# Watch-It-Board-1.net
KiCad netlist of a schematic drawn in EAGLE
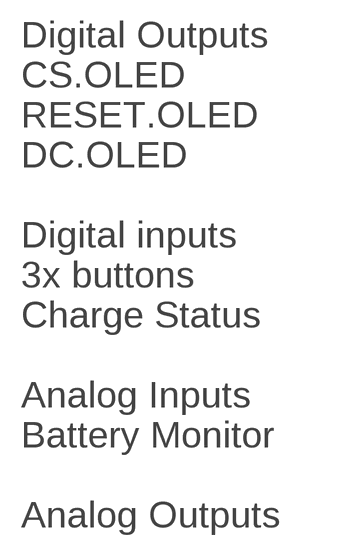
[diagram p0: schematic, sheet 1, part 1 of 2]
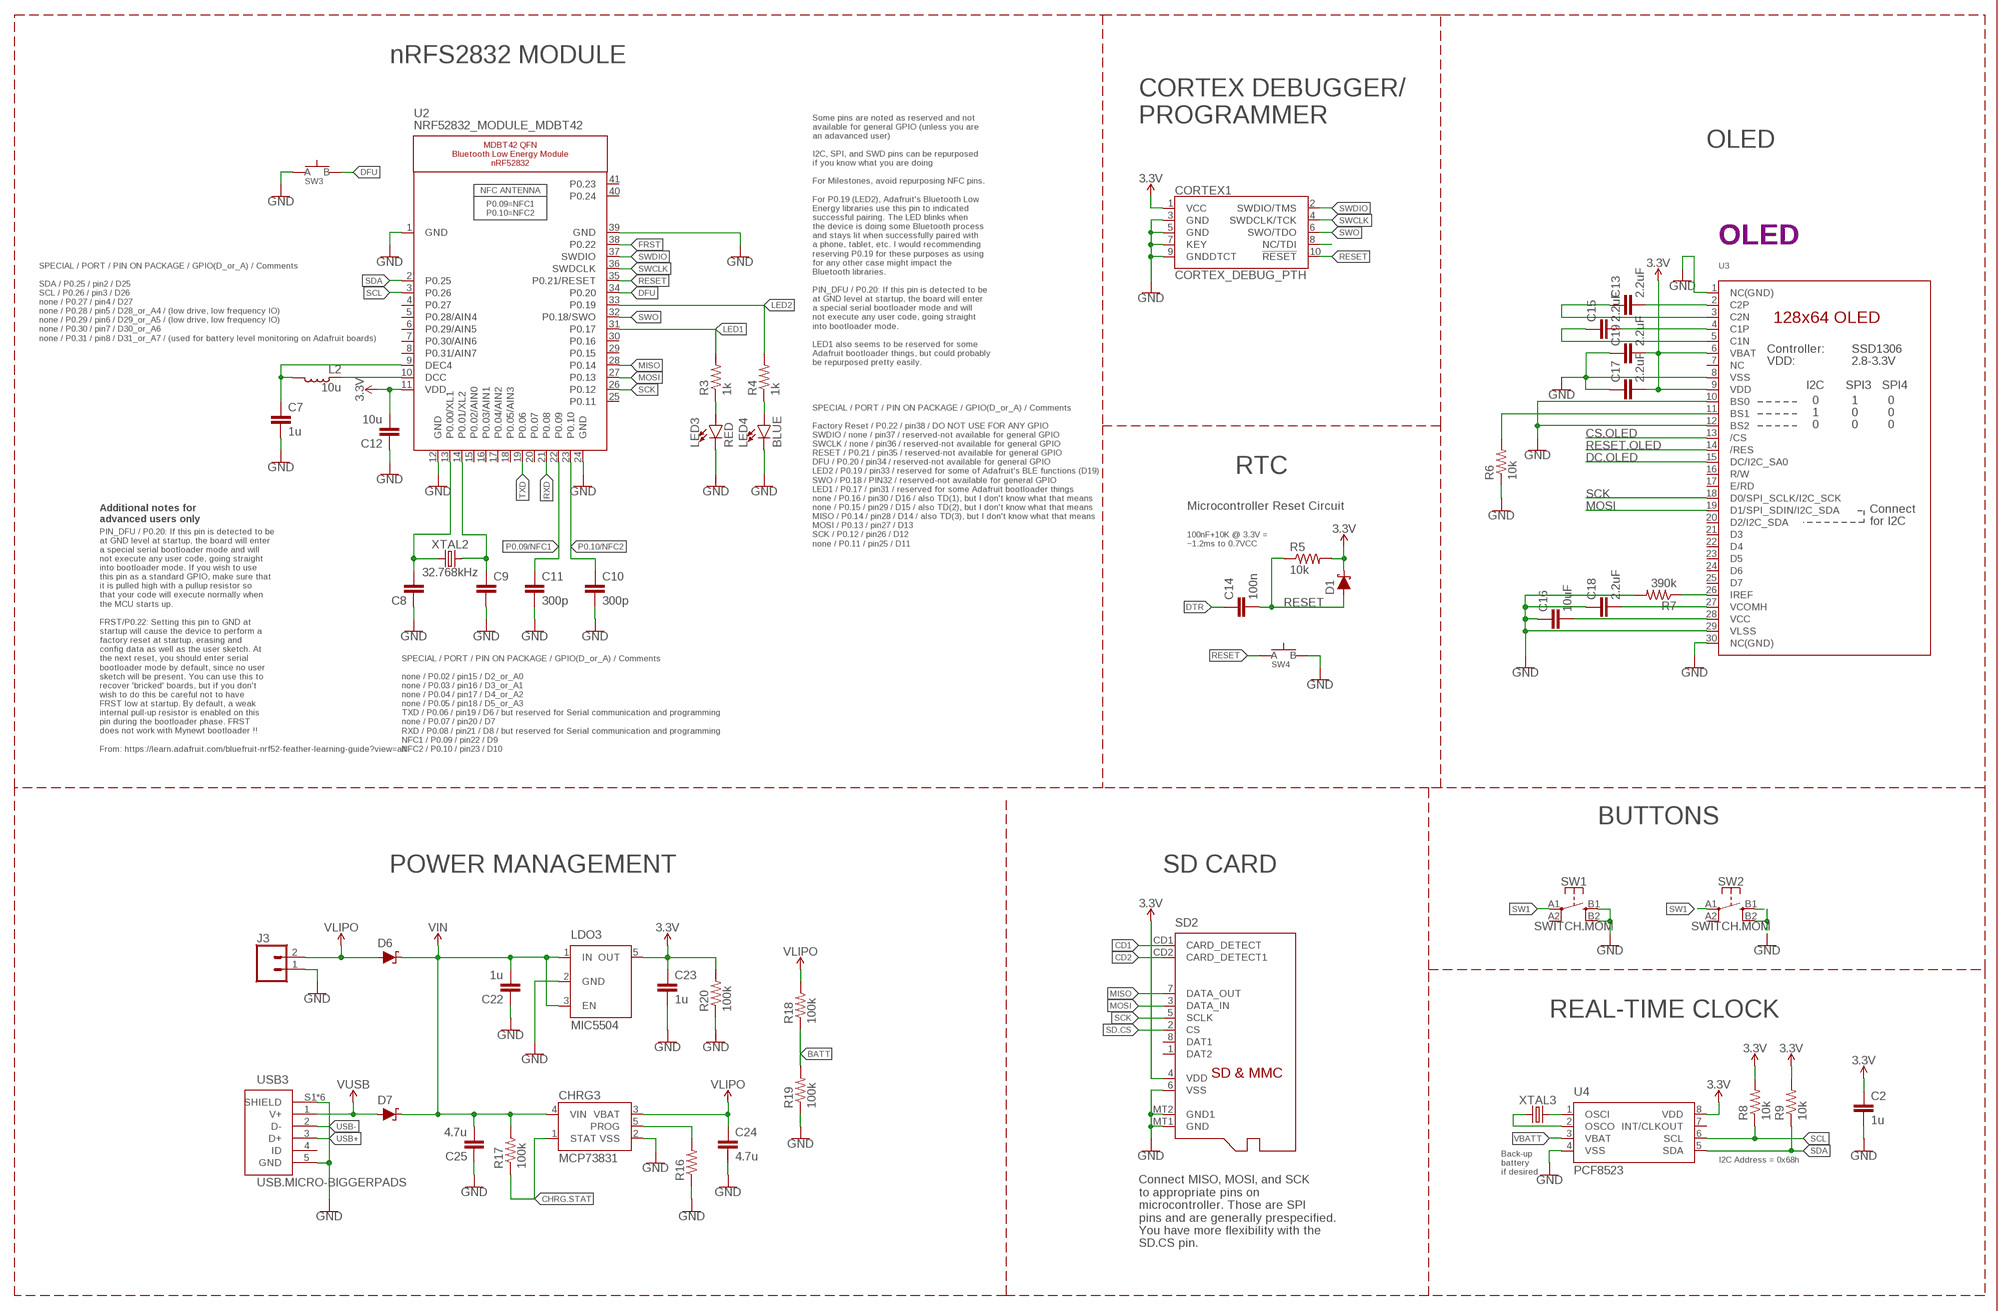
[diagram p1: schematic, sheet 1, part 2 of 2]

(export (version "E")
  (design (tool "Eeschema 10.0.6"))
  (components
    (comp (ref "C2")
      (value "1u")
      (footprint "eagle-import:C0603")
      (libsource (lib "eagle-import") (part "CAPACITOR0603"))
    )
    (comp (ref "C7")
      (value "1u")
      (footprint "eagle-import:C0603")
      (libsource (lib "eagle-import") (part "CAPACITOR0603"))
    )
    (comp (ref "C8")
      (value "CAPACITOR0603")
      (footprint "eagle-import:C0603")
      (libsource (lib "eagle-import") (part "CAPACITOR0603"))
    )
    (comp (ref "C9")
      (value "CAPACITOR0603")
      (footprint "eagle-import:C0603")
      (libsource (lib "eagle-import") (part "CAPACITOR0603"))
    )
    (comp (ref "C10")
      (value "300p")
      (footprint "eagle-import:C0603")
      (libsource (lib "eagle-import") (part "CAPACITOR0603"))
    )
    (comp (ref "C11")
      (value "300p")
      (footprint "eagle-import:C0603")
      (libsource (lib "eagle-import") (part "CAPACITOR0603"))
    )
    (comp (ref "C12")
      (value "10u")
      (footprint "eagle-import:C0805")
      (libsource (lib "eagle-import") (part "CAPACITOR0805"))
    )
    (comp (ref "C13")
      (value "2.2uF")
      (footprint "eagle-import:C0402")
      (libsource (lib "eagle-import") (part "CAPACITOR0402"))
    )
    (comp (ref "C14")
      (value "100n")
      (footprint "eagle-import:C0603")
      (libsource (lib "eagle-import") (part "CAPACITOR0603"))
    )
    (comp (ref "C15")
      (value "2.2uF")
      (footprint "eagle-import:C0402")
      (libsource (lib "eagle-import") (part "CAPACITOR0402"))
    )
    (comp (ref "C16")
      (value "10uF")
      (footprint "eagle-import:C0603")
      (libsource (lib "eagle-import") (part "CAPACITOR0603"))
    )
    (comp (ref "C17")
      (value "2.2uF")
      (footprint "eagle-import:C0402")
      (libsource (lib "eagle-import") (part "CAPACITOR0402"))
    )
    (comp (ref "C18")
      (value "2.2uF")
      (footprint "eagle-import:C0402")
      (libsource (lib "eagle-import") (part "CAPACITOR0402"))
    )
    (comp (ref "C19")
      (value "2.2uF")
      (footprint "eagle-import:C0402")
      (libsource (lib "eagle-import") (part "CAPACITOR0402"))
    )
    (comp (ref "C22")
      (value "1u")
      (footprint "eagle-import:C0603")
      (libsource (lib "eagle-import") (part "CAPACITOR0603"))
    )
    (comp (ref "C23")
      (value "1u")
      (footprint "eagle-import:C0603")
      (libsource (lib "eagle-import") (part "CAPACITOR0603"))
    )
    (comp (ref "C24")
      (value "4.7u")
      (footprint "eagle-import:C0603")
      (libsource (lib "eagle-import") (part "CAPACITOR0603"))
    )
    (comp (ref "C25")
      (value "4.7u")
      (footprint "eagle-import:C0603")
      (libsource (lib "eagle-import") (part "CAPACITOR0603"))
    )
    (comp (ref "CHRG3")
      (value "MCP73831")
      (footprint "eagle-import:SOT23-5")
      (libsource (lib "eagle-import") (part "MCP73831"))
    )
    (comp (ref "CORTEX1")
      (value "CORTEX_DEBUG_PTH")
      (footprint "eagle-import:2X5-PTH-1.27MM")
      (libsource (lib "eagle-import") (part "CORTEX_DEBUG_PTH"))
    )
    (comp (ref "D1")
      (value "SCHOTTKY-USC")
      (footprint "eagle-import:USC")
      (libsource (lib "eagle-import") (part "SCHOTTKY-USC"))
    )
    (comp (ref "D6")
      (value "SCHOTTKY-USC")
      (footprint "eagle-import:USC")
      (libsource (lib "eagle-import") (part "SCHOTTKY-USC"))
    )
    (comp (ref "D7")
      (value "SCHOTTKY-USC")
      (footprint "eagle-import:USC")
      (libsource (lib "eagle-import") (part "SCHOTTKY-USC"))
    )
    (comp (ref "J3")
      (value "CONN_02")
      (footprint "eagle-import:1X02")
      (libsource (lib "eagle-import") (part "CONN_02"))
    )
    (comp (ref "L2")
      (value "10u")
      (footprint "eagle-import:L0603")
      (libsource (lib "eagle-import") (part "INDUCTOR0603"))
    )
    (comp (ref "LDO3")
      (value "MIC5504")
      (footprint "eagle-import:SOT23-5")
      (libsource (lib "eagle-import") (part "MIC5504"))
    )
    (comp (ref "LED3")
      (value "RED")
      (footprint "eagle-import:LED-0603")
      (libsource (lib "eagle-import") (part "LED0603"))
    )
    (comp (ref "LED4")
      (value "BLUE")
      (footprint "eagle-import:LED-0603")
      (libsource (lib "eagle-import") (part "LED0603"))
    )
    (comp (ref "R3")
      (value "1k")
      (footprint "eagle-import:R0603")
      (libsource (lib "eagle-import") (part "RESISTOR0603"))
    )
    (comp (ref "R4")
      (value "1k")
      (footprint "eagle-import:R0603")
      (libsource (lib "eagle-import") (part "RESISTOR0603"))
    )
    (comp (ref "R5")
      (value "10k")
      (footprint "eagle-import:R0603")
      (libsource (lib "eagle-import") (part "RESISTOR0603"))
    )
    (comp (ref "R6")
      (value "10k")
      (footprint "eagle-import:R0603")
      (libsource (lib "eagle-import") (part "RESISTOR0603"))
    )
    (comp (ref "R7")
      (value "390k")
      (footprint "eagle-import:R0603")
      (libsource (lib "eagle-import") (part "RESISTOR0603"))
    )
    (comp (ref "R8")
      (value "10k")
      (footprint "eagle-import:R0603")
      (libsource (lib "eagle-import") (part "RESISTOR0603"))
    )
    (comp (ref "R9")
      (value "10k")
      (footprint "eagle-import:R0603")
      (libsource (lib "eagle-import") (part "RESISTOR0603"))
    )
    (comp (ref "R16")
      (value "RESISTOR0603")
      (footprint "eagle-import:R0603")
      (libsource (lib "eagle-import") (part "RESISTOR0603"))
    )
    (comp (ref "R17")
      (value "100k")
      (footprint "eagle-import:R0603")
      (libsource (lib "eagle-import") (part "RESISTOR0603"))
    )
    (comp (ref "R18")
      (value "100k")
      (footprint "eagle-import:R0603")
      (libsource (lib "eagle-import") (part "RESISTOR0603"))
    )
    (comp (ref "R19")
      (value "100k")
      (footprint "eagle-import:R0603")
      (libsource (lib "eagle-import") (part "RESISTOR0603"))
    )
    (comp (ref "R20")
      (value "100k")
      (footprint "eagle-import:R0603")
      (libsource (lib "eagle-import") (part "RESISTOR0603"))
    )
    (comp (ref "SD2")
      (value "MICROSD")
      (footprint "eagle-import:MICROSD")
      (libsource (lib "eagle-import") (part "MICROSD"))
    )
    (comp (ref "SW1")
      (value "SWITCH.MOM")
      (footprint "eagle-import:TACTILE_SWITCH_SMD_6.2MM_TALL")
      (libsource (lib "eagle-import") (part "SWITCH.MOM"))
    )
    (comp (ref "SW2")
      (value "SWITCH.MOM")
      (footprint "eagle-import:TACTILE_SWITCH_SMD_6.2MM_TALL")
      (libsource (lib "eagle-import") (part "SWITCH.MOM"))
    )
    (comp (ref "SW3")
      (value "SPST-PTS830GG140-COPY.1-3")
      (footprint "eagle-import:BUTTON-GULLWING")
      (libsource (lib "eagle-import") (part "SPST-PTS830GG140-COPY.1-3"))
    )
    (comp (ref "SW4")
      (value "SPST-PTS830GG140-COPY.1-3")
      (footprint "eagle-import:BUTTON-GULLWING")
      (libsource (lib "eagle-import") (part "SPST-PTS830GG140-COPY.1-3"))
    )
    (comp (ref "U2")
      (value "NRF52832_MODULE_MDBT42")
      (footprint "eagle-import:BLE_MODULE_RAYTAC_MDBT42")
      (libsource (lib "eagle-import") (part "NRF52832_MODULE_MDBT42"))
    )
    (comp (ref "U3")
      (value "DISP_OLED_UG-2864HSWEG01-NO-WRAPAROUND")
      (footprint "eagle-import:UG-2864HSWEG01_0.96IN_NO-WRAPAROUND")
      (libsource (lib "eagle-import") (part "DISP_OLED_UG-2864HSWEG01-NO-WRAPAROUND"))
    )
    (comp (ref "U4")
      (value "PCF8523")
      (footprint "eagle-import:SO8")
      (libsource (lib "eagle-import") (part "PCF8523"))
    )
    (comp (ref "USB3")
      (value "USB.MICRO-BIGGERPADS")
      (footprint "eagle-import:USB-MICRO-01.BIGGERPADS")
      (libsource (lib "eagle-import") (part "USB.MICRO-BIGGERPADS"))
    )
    (comp (ref "XTAL2")
      (value "32.768kHz")
      (footprint "eagle-import:2-SMD.NOLEAD.2.0MMTO1.2MM")
      (libsource (lib "eagle-import") (part "CRYSTALECS-.327-12.5-12-C-TR"))
    )
    (comp (ref "XTAL3")
      (value "32.7680kHz")
      (footprint "eagle-import:2-SMD.NOLEAD.2.0MMTO1.2MM")
      (fields (field (name "FREQ") "32.7680KHZ"))
      (libsource (lib "eagle-import") (part "CRYSTALECS-.327-12.5-12-C-TR"))
    )
  )
  (nets
    (net (code "1") (name "/CS.OLED") (class "Default")
      (node (ref "U3") (pin "13") (pinfunction "/CS_13") (pintype "input"))
    )
    (net (code "2") (name "/DC.OLED") (class "Default")
      (node (ref "U3") (pin "15") (pinfunction "DC/I2C_SA0_15") (pintype "input"))
    )
    (net (code "3") (name "/RESET.OLED") (class "Default")
      (node (ref "U3") (pin "14") (pinfunction "/RES_14") (pintype "input"))
    )
    (net (code "4") (name "3.3V") (class "Default")
      (node (ref "C12") (pin "2") (pinfunction "2_2") (pintype "passive"))
      (node (ref "C17") (pin "2") (pinfunction "2_2") (pintype "passive"))
      (node (ref "C19") (pin "2") (pinfunction "2_2") (pintype "passive"))
      (node (ref "C2") (pin "1") (pinfunction "1_1") (pintype "passive"))
      (node (ref "C23") (pin "1") (pinfunction "1_1") (pintype "passive"))
      (node (ref "CORTEX1") (pin "1") (pinfunction "VCC_1") (pintype "bidirectional"))
      (node (ref "D1") (pin "-") (pinfunction "C_-") (pintype "passive"))
      (node (ref "LDO3") (pin "5") (pinfunction "OUT_5") (pintype "bidirectional"))
      (node (ref "R20") (pin "2") (pinfunction "2_2") (pintype "passive"))
      (node (ref "R5") (pin "2") (pinfunction "2_2") (pintype "passive"))
      (node (ref "R8") (pin "2") (pinfunction "2_2") (pintype "passive"))
      (node (ref "R9") (pin "2") (pinfunction "2_2") (pintype "passive"))
      (node (ref "SD2") (pin "4") (pinfunction "VDD_4") (pintype "power_in"))
      (node (ref "U2") (pin "11") (pinfunction "VDD_11") (pintype "bidirectional"))
      (node (ref "U3") (pin "6") (pinfunction "VBAT_6") (pintype "input"))
      (node (ref "U3") (pin "9") (pinfunction "VDD_9") (pintype "power_in"))
      (node (ref "U4") (pin "8") (pinfunction "VDD_8") (pintype "power_in"))
    )
    (net (code "5") (name "BATT") (class "Default")
      (node (ref "R18") (pin "1") (pinfunction "1_1") (pintype "passive"))
      (node (ref "R19") (pin "2") (pinfunction "2_2") (pintype "passive"))
    )
    (net (code "6") (name "CD1") (class "Default")
      (node (ref "SD2") (pin "CD1") (pinfunction "CARD_DETECT_CD1") (pintype "passive"))
    )
    (net (code "7") (name "CD2") (class "Default")
      (node (ref "SD2") (pin "CD2") (pinfunction "CARD_DETECT1_CD2") (pintype "passive"))
    )
    (net (code "8") (name "CHRG.STAT") (class "Default")
      (node (ref "CHRG3") (pin "1") (pinfunction "STAT_1") (pintype "output"))
      (node (ref "R17") (pin "1") (pinfunction "1_1") (pintype "passive"))
    )
    (net (code "9") (name "DFU") (class "Default")
      (node (ref "SW3") (pin "3") (pinfunction "B_3") (pintype "bidirectional"))
      (node (ref "U2") (pin "34") (pinfunction "P0.20_34") (pintype "bidirectional"))
    )
    (net (code "10") (name "DTR") (class "Default")
      (node (ref "C14") (pin "1") (pinfunction "1_1") (pintype "passive"))
    )
    (net (code "11") (name "FRST") (class "Default")
      (node (ref "U2") (pin "38") (pinfunction "P0.22_38") (pintype "bidirectional"))
    )
    (net (code "12") (name "GND") (class "Default")
      (node (ref "C10") (pin "2") (pinfunction "2_2") (pintype "passive"))
      (node (ref "C11") (pin "2") (pinfunction "2_2") (pintype "passive"))
      (node (ref "C12") (pin "1") (pinfunction "1_1") (pintype "passive"))
      (node (ref "C16") (pin "1") (pinfunction "1_1") (pintype "passive"))
      (node (ref "C17") (pin "1") (pinfunction "1_1") (pintype "passive"))
      (node (ref "C18") (pin "1") (pinfunction "1_1") (pintype "passive"))
      (node (ref "C19") (pin "1") (pinfunction "1_1") (pintype "passive"))
      (node (ref "C2") (pin "2") (pinfunction "2_2") (pintype "passive"))
      (node (ref "C22") (pin "1") (pinfunction "1_1") (pintype "passive"))
      (node (ref "C23") (pin "2") (pinfunction "2_2") (pintype "passive"))
      (node (ref "C24") (pin "2") (pinfunction "2_2") (pintype "passive"))
      (node (ref "C25") (pin "1") (pinfunction "1_1") (pintype "passive"))
      (node (ref "C7") (pin "2") (pinfunction "2_2") (pintype "passive"))
      (node (ref "C8") (pin "1") (pinfunction "1_1") (pintype "passive"))
      (node (ref "C9") (pin "2") (pinfunction "2_2") (pintype "passive"))
      (node (ref "CHRG3") (pin "2") (pinfunction "VSS_2") (pintype "power_in"))
      (node (ref "CORTEX1") (pin "3") (pinfunction "GND_3") (pintype "bidirectional"))
      (node (ref "CORTEX1") (pin "5") (pinfunction "GND_5") (pintype "bidirectional"))
      (node (ref "CORTEX1") (pin "7") (pinfunction "KEY_7") (pintype "bidirectional"))
      (node (ref "CORTEX1") (pin "9") (pinfunction "GNDDTCT_9") (pintype "bidirectional"))
      (node (ref "J3") (pin "1") (pinfunction "1_1") (pintype "passive"))
      (node (ref "LDO3") (pin "2") (pinfunction "GND_2") (pintype "bidirectional"))
      (node (ref "LED3") (pin "C") (pinfunction "C_C") (pintype "passive"))
      (node (ref "LED4") (pin "C") (pinfunction "C_C") (pintype "passive"))
      (node (ref "R16") (pin "1") (pinfunction "1_1") (pintype "passive"))
      (node (ref "R19") (pin "1") (pinfunction "1_1") (pintype "passive"))
      (node (ref "R20") (pin "1") (pinfunction "1_1") (pintype "passive"))
      (node (ref "R6") (pin "1") (pinfunction "1_1") (pintype "passive"))
      (node (ref "R7") (pin "2") (pinfunction "2_2") (pintype "passive"))
      (node (ref "SD2") (pin "6") (pinfunction "VSS_6") (pintype "power_in"))
      (node (ref "SD2") (pin "MT1") (pinfunction "GND_MT1") (pintype "power_in"))
      (node (ref "SD2") (pin "MT2") (pinfunction "GND1_MT2") (pintype "power_in"))
      (node (ref "SW1") (pin "B1") (pinfunction "3_B1") (pintype "passive"))
      (node (ref "SW1") (pin "B2") (pinfunction "4_B2") (pintype "passive"))
      (node (ref "SW2") (pin "B1") (pinfunction "3_B1") (pintype "passive"))
      (node (ref "SW2") (pin "B2") (pinfunction "4_B2") (pintype "passive"))
      (node (ref "SW3") (pin "1") (pinfunction "A_1") (pintype "bidirectional"))
      (node (ref "SW4") (pin "3") (pinfunction "B_3") (pintype "bidirectional"))
      (node (ref "U2") (pin "1") (pinfunction "GND_1") (pintype "bidirectional"))
      (node (ref "U2") (pin "12") (pinfunction "GND_12") (pintype "bidirectional"))
      (node (ref "U2") (pin "24") (pinfunction "GND_24") (pintype "bidirectional"))
      (node (ref "U2") (pin "39") (pinfunction "GND_39") (pintype "bidirectional"))
      (node (ref "U3") (pin "1") (pinfunction "NC(GND)_1") (pintype "input"))
      (node (ref "U3") (pin "10") (pinfunction "BS0_10") (pintype "input"))
      (node (ref "U3") (pin "12") (pinfunction "BS2_12") (pintype "input"))
      (node (ref "U3") (pin "29") (pinfunction "VLSS_29") (pintype "power_in"))
      (node (ref "U3") (pin "30") (pinfunction "NC(GND)_30") (pintype "input"))
      (node (ref "U3") (pin "8") (pinfunction "VSS_8") (pintype "power_in"))
      (node (ref "U4") (pin "4") (pinfunction "VSS_4") (pintype "power_in"))
      (node (ref "USB3") (pin "5") (pinfunction "GND_5") (pintype "bidirectional"))
      (node (ref "USB3") (pin "S1") (pinfunction "SHIELD_S1") (pintype "bidirectional"))
      (node (ref "USB3") (pin "S2") (pinfunction "SHIELD_S2") (pintype "bidirectional"))
      (node (ref "USB3") (pin "S3") (pinfunction "SHIELD_S3") (pintype "bidirectional"))
      (node (ref "USB3") (pin "S4") (pinfunction "SHIELD_S4") (pintype "bidirectional"))
      (node (ref "USB3") (pin "S5") (pinfunction "SHIELD_S5") (pintype "bidirectional"))
      (node (ref "USB3") (pin "S6") (pinfunction "SHIELD_S6") (pintype "bidirectional"))
    )
    (net (code "13") (name "LED1") (class "Default")
      (node (ref "R3") (pin "2") (pinfunction "2_2") (pintype "passive"))
      (node (ref "U2") (pin "31") (pinfunction "P0.17_31") (pintype "bidirectional"))
    )
    (net (code "14") (name "LED2") (class "Default")
      (node (ref "R4") (pin "2") (pinfunction "2_2") (pintype "passive"))
      (node (ref "U2") (pin "33") (pinfunction "P0.19_33") (pintype "bidirectional"))
    )
    (net (code "15") (name "MISO") (class "Default")
      (node (ref "SD2") (pin "7") (pinfunction "DATA_OUT_7") (pintype "output"))
      (node (ref "U2") (pin "28") (pinfunction "P0.14_28") (pintype "bidirectional"))
    )
    (net (code "16") (name "MOSI") (class "Default")
      (node (ref "SD2") (pin "3") (pinfunction "DATA_IN_3") (pintype "input"))
      (node (ref "U2") (pin "27") (pinfunction "P0.13_27") (pintype "bidirectional"))
      (node (ref "U3") (pin "19") (pinfunction "D1/SPI_SDIN/I2C_SDA_19") (pintype "bidirectional"))
    )
    (net (code "17") (name "Net-(CHRG3-PROG)") (class "Default")
      (node (ref "CHRG3") (pin "5") (pinfunction "PROG_5") (pintype "input"))
      (node (ref "R16") (pin "2") (pinfunction "2_2") (pintype "passive"))
    )
    (net (code "18") (name "Net-(LED3-PadA)") (class "Default")
      (node (ref "LED3") (pin "A") (pinfunction "A_A") (pintype "passive"))
      (node (ref "R3") (pin "1") (pinfunction "1_1") (pintype "passive"))
    )
    (net (code "19") (name "Net-(LED4-PadA)") (class "Default")
      (node (ref "LED4") (pin "A") (pinfunction "A_A") (pintype "passive"))
      (node (ref "R4") (pin "1") (pinfunction "1_1") (pintype "passive"))
    )
    (net (code "20") (name "Net-(U2-DCC)") (class "Default")
      (node (ref "L2") (pin "1") (pinfunction "1_1") (pintype "passive"))
      (node (ref "U2") (pin "10") (pinfunction "DCC_10") (pintype "bidirectional"))
    )
    (net (code "21") (name "Net-(U2-DEC4)") (class "Default")
      (node (ref "C7") (pin "1") (pinfunction "1_1") (pintype "passive"))
      (node (ref "L2") (pin "2") (pinfunction "2_2") (pintype "passive"))
      (node (ref "U2") (pin "9") (pinfunction "DEC4_9") (pintype "bidirectional"))
    )
    (net (code "22") (name "Net-(U2-P0.00{slash}XL1)") (class "Default")
      (node (ref "C8") (pin "2") (pinfunction "2_2") (pintype "passive"))
      (node (ref "U2") (pin "13") (pinfunction "P0.00/XL1_13") (pintype "bidirectional"))
      (node (ref "XTAL2") (pin "P$1") (pinfunction "1_P$1") (pintype "passive"))
    )
    (net (code "23") (name "Net-(U2-P0.01{slash}XL2)") (class "Default")
      (node (ref "C9") (pin "1") (pinfunction "1_1") (pintype "passive"))
      (node (ref "U2") (pin "14") (pinfunction "P0.01/XL2_14") (pintype "bidirectional"))
      (node (ref "XTAL2") (pin "P$2") (pinfunction "2_P$2") (pintype "passive"))
    )
    (net (code "24") (name "Net-(U3-BS1)") (class "Default")
      (node (ref "R6") (pin "2") (pinfunction "2_2") (pintype "passive"))
      (node (ref "U3") (pin "11") (pinfunction "BS1_11") (pintype "input"))
    )
    (net (code "25") (name "Net-(U3-C1N)") (class "Default")
      (node (ref "C15") (pin "1") (pinfunction "1_1") (pintype "passive"))
      (node (ref "U3") (pin "5") (pinfunction "C1N_5") (pintype "input"))
    )
    (net (code "26") (name "Net-(U3-C1P)") (class "Default")
      (node (ref "C15") (pin "2") (pinfunction "2_2") (pintype "passive"))
      (node (ref "U3") (pin "4") (pinfunction "C1P_4") (pintype "input"))
    )
    (net (code "27") (name "Net-(U3-C2N)") (class "Default")
      (node (ref "C13") (pin "1") (pinfunction "1_1") (pintype "passive"))
      (node (ref "U3") (pin "3") (pinfunction "C2N_3") (pintype "input"))
    )
    (net (code "28") (name "Net-(U3-C2P)") (class "Default")
      (node (ref "C13") (pin "2") (pinfunction "2_2") (pintype "passive"))
      (node (ref "U3") (pin "2") (pinfunction "C2P_2") (pintype "input"))
    )
    (net (code "29") (name "Net-(U3-IREF)") (class "Default")
      (node (ref "R7") (pin "1") (pinfunction "1_1") (pintype "passive"))
      (node (ref "U3") (pin "26") (pinfunction "IREF_26") (pintype "input"))
    )
    (net (code "30") (name "Net-(U3-VCC)") (class "Default")
      (node (ref "C16") (pin "2") (pinfunction "2_2") (pintype "passive"))
      (node (ref "U3") (pin "28") (pinfunction "VCC_28") (pintype "power_in"))
    )
    (net (code "31") (name "Net-(U3-VCOMH)") (class "Default")
      (node (ref "C18") (pin "2") (pinfunction "2_2") (pintype "passive"))
      (node (ref "U3") (pin "27") (pinfunction "VCOMH_27") (pintype "output"))
    )
    (net (code "32") (name "Net-(U4-OSCI)") (class "Default")
      (node (ref "U4") (pin "1") (pinfunction "OSCI_1") (pintype "bidirectional"))
      (node (ref "XTAL3") (pin "P$2") (pinfunction "2_P$2") (pintype "passive"))
    )
    (net (code "33") (name "Net-(U4-OSCO)") (class "Default")
      (node (ref "U4") (pin "2") (pinfunction "OSCO_2") (pintype "bidirectional"))
      (node (ref "XTAL3") (pin "P$1") (pinfunction "1_P$1") (pintype "passive"))
    )
    (net (code "34") (name "P0.09{slash}NFC1") (class "Default")
      (node (ref "C11") (pin "1") (pinfunction "1_1") (pintype "passive"))
      (node (ref "U2") (pin "22") (pinfunction "P0.09_22") (pintype "bidirectional"))
    )
    (net (code "35") (name "P0.10{slash}NFC2") (class "Default")
      (node (ref "C10") (pin "1") (pinfunction "1_1") (pintype "passive"))
      (node (ref "U2") (pin "23") (pinfunction "P0.10_23") (pintype "bidirectional"))
    )
    (net (code "36") (name "RESET") (class "Default")
      (node (ref "C14") (pin "2") (pinfunction "2_2") (pintype "passive"))
      (node (ref "CORTEX1") (pin "10") (pinfunction "~{RESET}_10") (pintype "bidirectional"))
      (node (ref "D1") (pin "+") (pinfunction "A_+") (pintype "passive"))
      (node (ref "R5") (pin "1") (pinfunction "1_1") (pintype "passive"))
      (node (ref "SW4") (pin "1") (pinfunction "A_1") (pintype "bidirectional"))
      (node (ref "U2") (pin "35") (pinfunction "P0.21/RESET_35") (pintype "bidirectional"))
    )
    (net (code "37") (name "RXD") (class "Default")
      (node (ref "U2") (pin "21") (pinfunction "P0.08_21") (pintype "bidirectional"))
    )
    (net (code "38") (name "SCK") (class "Default")
      (node (ref "SD2") (pin "5") (pinfunction "SCLK_5") (pintype "input"))
      (node (ref "U2") (pin "26") (pinfunction "P0.12_26") (pintype "bidirectional"))
      (node (ref "U3") (pin "18") (pinfunction "D0/SPI_SCLK/I2C_SCK_18") (pintype "bidirectional"))
    )
    (net (code "39") (name "SCL") (class "Default")
      (node (ref "R8") (pin "1") (pinfunction "1_1") (pintype "passive"))
      (node (ref "U2") (pin "3") (pinfunction "P0.26_3") (pintype "bidirectional"))
      (node (ref "U4") (pin "6") (pinfunction "SCL_6") (pintype "bidirectional"))
    )
    (net (code "40") (name "SD.CS") (class "Default")
      (node (ref "SD2") (pin "2") (pinfunction "CS_2") (pintype "input"))
    )
    (net (code "41") (name "SDA") (class "Default")
      (node (ref "R9") (pin "1") (pinfunction "1_1") (pintype "passive"))
      (node (ref "U2") (pin "2") (pinfunction "P0.25_2") (pintype "bidirectional"))
      (node (ref "U4") (pin "5") (pinfunction "SDA_5") (pintype "bidirectional"))
    )
    (net (code "42") (name "SW1") (class "Default")
      (node (ref "SW1") (pin "A1") (pinfunction "1_A1") (pintype "passive"))
      (node (ref "SW2") (pin "A1") (pinfunction "1_A1") (pintype "passive"))
    )
    (net (code "43") (name "SWCLK") (class "Default")
      (node (ref "CORTEX1") (pin "4") (pinfunction "SWDCLK/TCK_4") (pintype "bidirectional"))
      (node (ref "U2") (pin "36") (pinfunction "SWDCLK_36") (pintype "bidirectional"))
    )
    (net (code "44") (name "SWDIO") (class "Default")
      (node (ref "CORTEX1") (pin "2") (pinfunction "SWDIO/TMS_2") (pintype "bidirectional"))
      (node (ref "U2") (pin "37") (pinfunction "SWDIO_37") (pintype "bidirectional"))
    )
    (net (code "45") (name "SWO") (class "Default")
      (node (ref "CORTEX1") (pin "6") (pinfunction "SWO/TDO_6") (pintype "bidirectional"))
      (node (ref "U2") (pin "32") (pinfunction "P0.18/SWO_32") (pintype "bidirectional"))
    )
    (net (code "46") (name "TXD") (class "Default")
      (node (ref "U2") (pin "19") (pinfunction "P0.06_19") (pintype "bidirectional"))
    )
    (net (code "47") (name "USB+") (class "Default")
      (node (ref "USB3") (pin "3") (pinfunction "D+_3") (pintype "bidirectional"))
    )
    (net (code "48") (name "USB-") (class "Default")
      (node (ref "USB3") (pin "2") (pinfunction "D-_2") (pintype "bidirectional"))
    )
    (net (code "49") (name "VBATT") (class "Default")
      (node (ref "U4") (pin "3") (pinfunction "VBAT_3") (pintype "power_in"))
    )
    (net (code "50") (name "VIN") (class "Default")
      (node (ref "C22") (pin "2") (pinfunction "2_2") (pintype "passive"))
      (node (ref "C25") (pin "2") (pinfunction "2_2") (pintype "passive"))
      (node (ref "CHRG3") (pin "4") (pinfunction "VIN_4") (pintype "power_in"))
      (node (ref "D6") (pin "-") (pinfunction "C_-") (pintype "passive"))
      (node (ref "D7") (pin "-") (pinfunction "C_-") (pintype "passive"))
      (node (ref "LDO3") (pin "1") (pinfunction "IN_1") (pintype "bidirectional"))
      (node (ref "LDO3") (pin "3") (pinfunction "EN_3") (pintype "bidirectional"))
      (node (ref "R17") (pin "2") (pinfunction "2_2") (pintype "passive"))
    )
    (net (code "51") (name "VLIPO") (class "Default")
      (node (ref "C24") (pin "1") (pinfunction "1_1") (pintype "passive"))
      (node (ref "CHRG3") (pin "3") (pinfunction "VBAT_3") (pintype "power_in"))
      (node (ref "D6") (pin "+") (pinfunction "A_+") (pintype "passive"))
      (node (ref "J3") (pin "2") (pinfunction "2_2") (pintype "passive"))
      (node (ref "R18") (pin "2") (pinfunction "2_2") (pintype "passive"))
    )
    (net (code "52") (name "VUSB") (class "Default")
      (node (ref "D7") (pin "+") (pinfunction "A_+") (pintype "passive"))
      (node (ref "USB3") (pin "1") (pinfunction "V+_1") (pintype "bidirectional"))
    )
    (net (code "53") (name "unconnected-(CORTEX1-NC{slash}TDI-Pad8)") (class "Default")
      (node (ref "CORTEX1") (pin "8") (pinfunction "NC/TDI_8") (pintype "bidirectional"))
    )
    (net (code "54") (name "unconnected-(SD2-DAT1-Pad8)") (class "Default")
      (node (ref "SD2") (pin "8") (pinfunction "DAT1_8") (pintype "bidirectional"))
    )
    (net (code "55") (name "unconnected-(SD2-DAT2-Pad1)") (class "Default")
      (node (ref "SD2") (pin "1") (pinfunction "DAT2_1") (pintype "bidirectional"))
    )
    (net (code "56") (name "unconnected-(SW1-2-PadA2)") (class "Default")
      (node (ref "SW1") (pin "A2") (pinfunction "2_A2") (pintype "passive"))
    )
    (net (code "57") (name "unconnected-(SW2-2-PadA2)") (class "Default")
      (node (ref "SW2") (pin "A2") (pinfunction "2_A2") (pintype "passive"))
    )
    (net (code "58") (name "unconnected-(U2-P0.02{slash}AIN0-Pad15)") (class "Default")
      (node (ref "U2") (pin "15") (pinfunction "P0.02/AIN0_15") (pintype "bidirectional"))
    )
    (net (code "59") (name "unconnected-(U2-P0.03{slash}AIN1-Pad16)") (class "Default")
      (node (ref "U2") (pin "16") (pinfunction "P0.03/AIN1_16") (pintype "bidirectional"))
    )
    (net (code "60") (name "unconnected-(U2-P0.04{slash}AIN2-Pad17)") (class "Default")
      (node (ref "U2") (pin "17") (pinfunction "P0.04/AIN2_17") (pintype "bidirectional"))
    )
    (net (code "61") (name "unconnected-(U2-P0.05{slash}AIN3-Pad18)") (class "Default")
      (node (ref "U2") (pin "18") (pinfunction "P0.05/AIN3_18") (pintype "bidirectional"))
    )
    (net (code "62") (name "unconnected-(U2-P0.07-Pad20)") (class "Default")
      (node (ref "U2") (pin "20") (pinfunction "P0.07_20") (pintype "bidirectional"))
    )
    (net (code "63") (name "unconnected-(U2-P0.11-Pad25)") (class "Default")
      (node (ref "U2") (pin "25") (pinfunction "P0.11_25") (pintype "bidirectional"))
    )
    (net (code "64") (name "unconnected-(U2-P0.15-Pad29)") (class "Default")
      (node (ref "U2") (pin "29") (pinfunction "P0.15_29") (pintype "bidirectional"))
    )
    (net (code "65") (name "unconnected-(U2-P0.16-Pad30)") (class "Default")
      (node (ref "U2") (pin "30") (pinfunction "P0.16_30") (pintype "bidirectional"))
    )
    (net (code "66") (name "unconnected-(U2-P0.23-Pad41)") (class "Default")
      (node (ref "U2") (pin "41") (pinfunction "P0.23_41") (pintype "bidirectional"))
    )
    (net (code "67") (name "unconnected-(U2-P0.24-Pad40)") (class "Default")
      (node (ref "U2") (pin "40") (pinfunction "P0.24_40") (pintype "bidirectional"))
    )
    (net (code "68") (name "unconnected-(U2-P0.27-Pad4)") (class "Default")
      (node (ref "U2") (pin "4") (pinfunction "P0.27_4") (pintype "bidirectional"))
    )
    (net (code "69") (name "unconnected-(U2-P0.28{slash}AIN4-Pad5)") (class "Default")
      (node (ref "U2") (pin "5") (pinfunction "P0.28/AIN4_5") (pintype "bidirectional"))
    )
    (net (code "70") (name "unconnected-(U2-P0.29{slash}AIN5-Pad6)") (class "Default")
      (node (ref "U2") (pin "6") (pinfunction "P0.29/AIN5_6") (pintype "bidirectional"))
    )
    (net (code "71") (name "unconnected-(U2-P0.30{slash}AIN6-Pad7)") (class "Default")
      (node (ref "U2") (pin "7") (pinfunction "P0.30/AIN6_7") (pintype "bidirectional"))
    )
    (net (code "72") (name "unconnected-(U2-P0.31{slash}AIN7-Pad8)") (class "Default")
      (node (ref "U2") (pin "8") (pinfunction "P0.31/AIN7_8") (pintype "bidirectional"))
    )
    (net (code "73") (name "unconnected-(U3-D2{slash}I2C_SDA-Pad20)") (class "Default")
      (node (ref "U3") (pin "20") (pinfunction "D2/I2C_SDA_20") (pintype "bidirectional"))
    )
    (net (code "74") (name "unconnected-(U3-D3-Pad21)") (class "Default")
      (node (ref "U3") (pin "21") (pinfunction "D3_21") (pintype "bidirectional"))
    )
    (net (code "75") (name "unconnected-(U3-D4-Pad22)") (class "Default")
      (node (ref "U3") (pin "22") (pinfunction "D4_22") (pintype "bidirectional"))
    )
    (net (code "76") (name "unconnected-(U3-D5-Pad23)") (class "Default")
      (node (ref "U3") (pin "23") (pinfunction "D5_23") (pintype "bidirectional"))
    )
    (net (code "77") (name "unconnected-(U3-D6-Pad24)") (class "Default")
      (node (ref "U3") (pin "24") (pinfunction "D6_24") (pintype "bidirectional"))
    )
    (net (code "78") (name "unconnected-(U3-D7-Pad25)") (class "Default")
      (node (ref "U3") (pin "25") (pinfunction "D7_25") (pintype "bidirectional"))
    )
    (net (code "79") (name "unconnected-(U3-E{slash}RD-Pad17)") (class "Default")
      (node (ref "U3") (pin "17") (pinfunction "E/RD_17") (pintype "input"))
    )
    (net (code "80") (name "unconnected-(U3-NC-Pad7)") (class "Default")
      (node (ref "U3") (pin "7") (pinfunction "NC_7") (pintype "no_connect"))
    )
    (net (code "81") (name "unconnected-(U3-R{slash}W-Pad16)") (class "Default")
      (node (ref "U3") (pin "16") (pinfunction "R/W_16") (pintype "input"))
    )
    (net (code "82") (name "unconnected-(U4-INT{slash}CLKOUT-Pad7)") (class "Default")
      (node (ref "U4") (pin "7") (pinfunction "INT/CLKOUT_7") (pintype "bidirectional"))
    )
    (net (code "83") (name "unconnected-(USB3-ID-Pad4)") (class "Default")
      (node (ref "USB3") (pin "4") (pinfunction "ID_4") (pintype "bidirectional"))
    )
  )
)
